# AFR_bar.net
KiCad netlist of a schematic drawn in Altium Designer
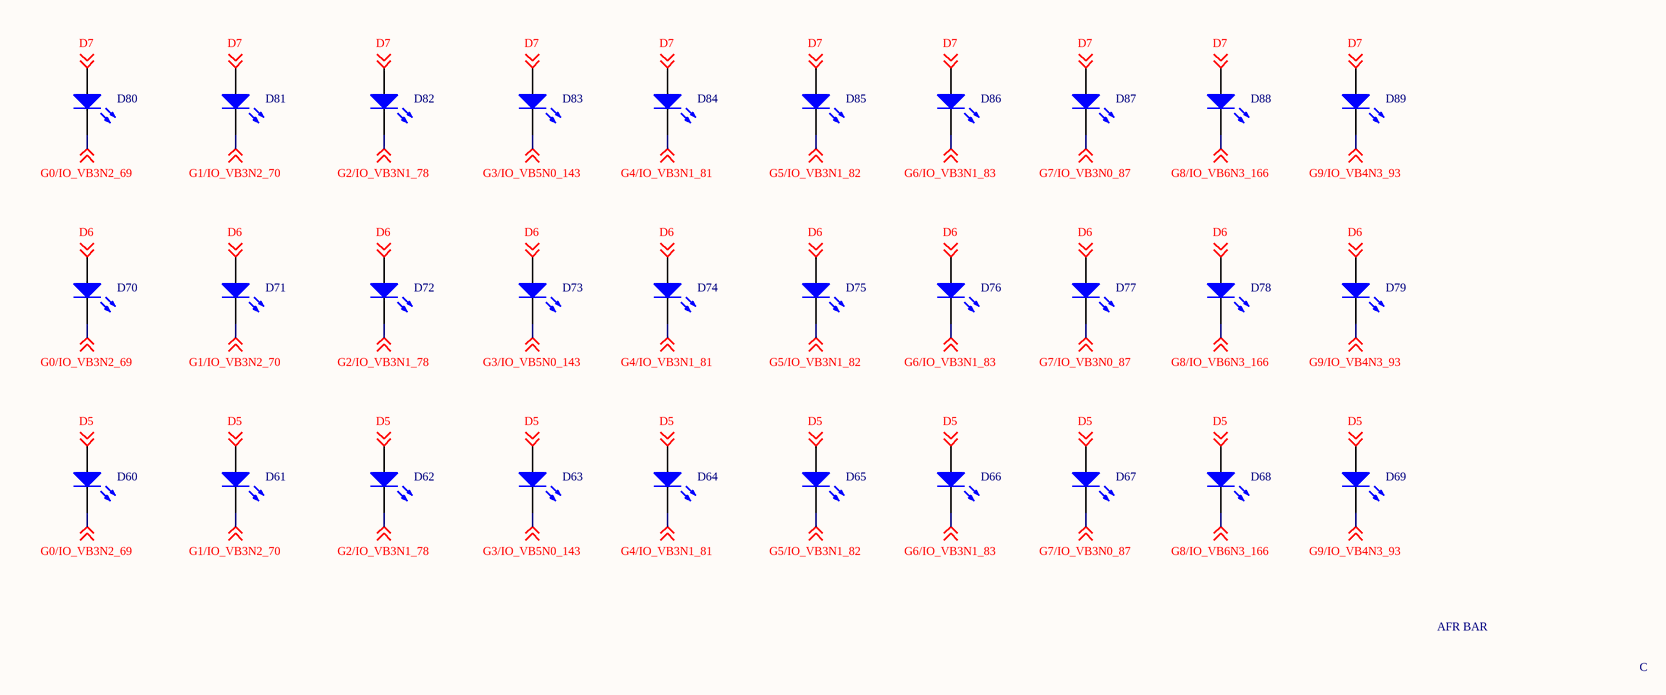
[diagram p0: AFR_bar.SchDoc]

(export (version "E")
  (design (tool "Eeschema 10.0.6"))
  (components
    (comp (ref "D60")
      (value "~")
      (footprint "DIODE_0603")
      (description "Typical INFRARED GaAs LED")
      (fields (field (name "PUBLISHER") "Altium Limited"))
      (libsource (lib "Miscellaneous Devices") (part "LED0"))
    )
    (comp (ref "D61")
      (value "~")
      (footprint "DIODE_0603")
      (description "Typical INFRARED GaAs LED")
      (fields (field (name "PUBLISHER") "Altium Limited"))
      (libsource (lib "Miscellaneous Devices") (part "LED0"))
    )
    (comp (ref "D62")
      (value "~")
      (footprint "DIODE_0603")
      (description "Typical INFRARED GaAs LED")
      (fields (field (name "PUBLISHER") "Altium Limited"))
      (libsource (lib "Miscellaneous Devices") (part "LED0"))
    )
    (comp (ref "D63")
      (value "~")
      (footprint "DIODE_0603")
      (description "Typical INFRARED GaAs LED")
      (fields (field (name "PUBLISHER") "Altium Limited"))
      (libsource (lib "Miscellaneous Devices") (part "LED0"))
    )
    (comp (ref "D64")
      (value "~")
      (footprint "DIODE_0603")
      (description "Typical INFRARED GaAs LED")
      (fields (field (name "PUBLISHER") "Altium Limited"))
      (libsource (lib "Miscellaneous Devices") (part "LED0"))
    )
    (comp (ref "D65")
      (value "~")
      (footprint "DIODE_0603")
      (description "Typical INFRARED GaAs LED")
      (fields (field (name "PUBLISHER") "Altium Limited"))
      (libsource (lib "Miscellaneous Devices") (part "LED0"))
    )
    (comp (ref "D66")
      (value "~")
      (footprint "DIODE_0603")
      (description "Typical INFRARED GaAs LED")
      (fields (field (name "PUBLISHER") "Altium Limited"))
      (libsource (lib "Miscellaneous Devices") (part "LED0"))
    )
    (comp (ref "D67")
      (value "~")
      (footprint "DIODE_0603")
      (description "Typical INFRARED GaAs LED")
      (fields (field (name "PUBLISHER") "Altium Limited"))
      (libsource (lib "Miscellaneous Devices") (part "LED0"))
    )
    (comp (ref "D68")
      (value "~")
      (footprint "DIODE_0603")
      (description "Typical INFRARED GaAs LED")
      (fields (field (name "PUBLISHER") "Altium Limited"))
      (libsource (lib "Miscellaneous Devices") (part "LED0"))
    )
    (comp (ref "D69")
      (value "~")
      (footprint "DIODE_0603")
      (description "Typical INFRARED GaAs LED")
      (fields (field (name "PUBLISHER") "Altium Limited"))
      (libsource (lib "Miscellaneous Devices") (part "LED0"))
    )
    (comp (ref "D70")
      (value "~")
      (footprint "DIODE_0603")
      (description "Typical INFRARED GaAs LED")
      (fields (field (name "PUBLISHER") "Altium Limited"))
      (libsource (lib "Miscellaneous Devices") (part "LED0"))
    )
    (comp (ref "D71")
      (value "~")
      (footprint "DIODE_0603")
      (description "Typical INFRARED GaAs LED")
      (fields (field (name "PUBLISHER") "Altium Limited"))
      (libsource (lib "Miscellaneous Devices") (part "LED0"))
    )
    (comp (ref "D72")
      (value "~")
      (footprint "DIODE_0603")
      (description "Typical INFRARED GaAs LED")
      (fields (field (name "PUBLISHER") "Altium Limited"))
      (libsource (lib "Miscellaneous Devices") (part "LED0"))
    )
    (comp (ref "D73")
      (value "~")
      (footprint "DIODE_0603")
      (description "Typical INFRARED GaAs LED")
      (fields (field (name "PUBLISHER") "Altium Limited"))
      (libsource (lib "Miscellaneous Devices") (part "LED0"))
    )
    (comp (ref "D74")
      (value "~")
      (footprint "DIODE_0603")
      (description "Typical INFRARED GaAs LED")
      (fields (field (name "PUBLISHER") "Altium Limited"))
      (libsource (lib "Miscellaneous Devices") (part "LED0"))
    )
    (comp (ref "D75")
      (value "~")
      (footprint "DIODE_0603")
      (description "Typical INFRARED GaAs LED")
      (fields (field (name "PUBLISHER") "Altium Limited"))
      (libsource (lib "Miscellaneous Devices") (part "LED0"))
    )
    (comp (ref "D76")
      (value "~")
      (footprint "DIODE_0603")
      (description "Typical INFRARED GaAs LED")
      (fields (field (name "PUBLISHER") "Altium Limited"))
      (libsource (lib "Miscellaneous Devices") (part "LED0"))
    )
    (comp (ref "D77")
      (value "~")
      (footprint "DIODE_0603")
      (description "Typical INFRARED GaAs LED")
      (fields (field (name "PUBLISHER") "Altium Limited"))
      (libsource (lib "Miscellaneous Devices") (part "LED0"))
    )
    (comp (ref "D78")
      (value "~")
      (footprint "DIODE_0603")
      (description "Typical INFRARED GaAs LED")
      (fields (field (name "PUBLISHER") "Altium Limited"))
      (libsource (lib "Miscellaneous Devices") (part "LED0"))
    )
    (comp (ref "D79")
      (value "~")
      (footprint "DIODE_0603")
      (description "Typical INFRARED GaAs LED")
      (fields (field (name "PUBLISHER") "Altium Limited"))
      (libsource (lib "Miscellaneous Devices") (part "LED0"))
    )
    (comp (ref "D80")
      (value "~")
      (footprint "DIODE_0603")
      (description "Typical INFRARED GaAs LED")
      (fields (field (name "PUBLISHER") "Altium Limited"))
      (libsource (lib "Miscellaneous Devices") (part "LED0"))
    )
    (comp (ref "D81")
      (value "~")
      (footprint "DIODE_0603")
      (description "Typical INFRARED GaAs LED")
      (fields (field (name "PUBLISHER") "Altium Limited"))
      (libsource (lib "Miscellaneous Devices") (part "LED0"))
    )
    (comp (ref "D82")
      (value "~")
      (footprint "DIODE_0603")
      (description "Typical INFRARED GaAs LED")
      (fields (field (name "PUBLISHER") "Altium Limited"))
      (libsource (lib "Miscellaneous Devices") (part "LED0"))
    )
    (comp (ref "D83")
      (value "~")
      (footprint "DIODE_0603")
      (description "Typical INFRARED GaAs LED")
      (fields (field (name "PUBLISHER") "Altium Limited"))
      (libsource (lib "Miscellaneous Devices") (part "LED0"))
    )
    (comp (ref "D84")
      (value "~")
      (footprint "DIODE_0603")
      (description "Typical INFRARED GaAs LED")
      (fields (field (name "PUBLISHER") "Altium Limited"))
      (libsource (lib "Miscellaneous Devices") (part "LED0"))
    )
    (comp (ref "D85")
      (value "~")
      (footprint "DIODE_0603")
      (description "Typical INFRARED GaAs LED")
      (fields (field (name "PUBLISHER") "Altium Limited"))
      (libsource (lib "Miscellaneous Devices") (part "LED0"))
    )
    (comp (ref "D86")
      (value "~")
      (footprint "DIODE_0603")
      (description "Typical INFRARED GaAs LED")
      (fields (field (name "PUBLISHER") "Altium Limited"))
      (libsource (lib "Miscellaneous Devices") (part "LED0"))
    )
    (comp (ref "D87")
      (value "~")
      (footprint "DIODE_0603")
      (description "Typical INFRARED GaAs LED")
      (fields (field (name "PUBLISHER") "Altium Limited"))
      (libsource (lib "Miscellaneous Devices") (part "LED0"))
    )
    (comp (ref "D88")
      (value "~")
      (footprint "DIODE_0603")
      (description "Typical INFRARED GaAs LED")
      (fields (field (name "PUBLISHER") "Altium Limited"))
      (libsource (lib "Miscellaneous Devices") (part "LED0"))
    )
    (comp (ref "D89")
      (value "~")
      (footprint "DIODE_0603")
      (description "Typical INFRARED GaAs LED")
      (fields (field (name "PUBLISHER") "Altium Limited"))
      (libsource (lib "Miscellaneous Devices") (part "LED0"))
    )
  )
  (nets
    (net (code "1") (name "D5") (class "Default")
      (node (ref "D60") (pin "1") (pinfunction "A_1") (pintype "passive"))
      (node (ref "D61") (pin "1") (pinfunction "A_1") (pintype "passive"))
      (node (ref "D62") (pin "1") (pinfunction "A_1") (pintype "passive"))
      (node (ref "D63") (pin "1") (pinfunction "A_1") (pintype "passive"))
      (node (ref "D64") (pin "1") (pinfunction "A_1") (pintype "passive"))
      (node (ref "D65") (pin "1") (pinfunction "A_1") (pintype "passive"))
      (node (ref "D66") (pin "1") (pinfunction "A_1") (pintype "passive"))
      (node (ref "D67") (pin "1") (pinfunction "A_1") (pintype "passive"))
      (node (ref "D68") (pin "1") (pinfunction "A_1") (pintype "passive"))
      (node (ref "D69") (pin "1") (pinfunction "A_1") (pintype "passive"))
    )
    (net (code "2") (name "D6") (class "Default")
      (node (ref "D70") (pin "1") (pinfunction "A_1") (pintype "passive"))
      (node (ref "D71") (pin "1") (pinfunction "A_1") (pintype "passive"))
      (node (ref "D72") (pin "1") (pinfunction "A_1") (pintype "passive"))
      (node (ref "D73") (pin "1") (pinfunction "A_1") (pintype "passive"))
      (node (ref "D74") (pin "1") (pinfunction "A_1") (pintype "passive"))
      (node (ref "D75") (pin "1") (pinfunction "A_1") (pintype "passive"))
      (node (ref "D76") (pin "1") (pinfunction "A_1") (pintype "passive"))
      (node (ref "D77") (pin "1") (pinfunction "A_1") (pintype "passive"))
      (node (ref "D78") (pin "1") (pinfunction "A_1") (pintype "passive"))
      (node (ref "D79") (pin "1") (pinfunction "A_1") (pintype "passive"))
    )
    (net (code "3") (name "D7") (class "Default")
      (node (ref "D80") (pin "1") (pinfunction "A_1") (pintype "passive"))
      (node (ref "D81") (pin "1") (pinfunction "A_1") (pintype "passive"))
      (node (ref "D82") (pin "1") (pinfunction "A_1") (pintype "passive"))
      (node (ref "D83") (pin "1") (pinfunction "A_1") (pintype "passive"))
      (node (ref "D84") (pin "1") (pinfunction "A_1") (pintype "passive"))
      (node (ref "D85") (pin "1") (pinfunction "A_1") (pintype "passive"))
      (node (ref "D86") (pin "1") (pinfunction "A_1") (pintype "passive"))
      (node (ref "D87") (pin "1") (pinfunction "A_1") (pintype "passive"))
      (node (ref "D88") (pin "1") (pinfunction "A_1") (pintype "passive"))
      (node (ref "D89") (pin "1") (pinfunction "A_1") (pintype "passive"))
    )
    (net (code "4") (name "G0{slash}IO_VB3N2_69") (class "Default")
      (node (ref "D60") (pin "2") (pinfunction "K_2") (pintype "passive"))
      (node (ref "D70") (pin "2") (pinfunction "K_2") (pintype "passive"))
      (node (ref "D80") (pin "2") (pinfunction "K_2") (pintype "passive"))
    )
    (net (code "5") (name "G1{slash}IO_VB3N2_70") (class "Default")
      (node (ref "D61") (pin "2") (pinfunction "K_2") (pintype "passive"))
      (node (ref "D71") (pin "2") (pinfunction "K_2") (pintype "passive"))
      (node (ref "D81") (pin "2") (pinfunction "K_2") (pintype "passive"))
    )
    (net (code "6") (name "G2{slash}IO_VB3N1_78") (class "Default")
      (node (ref "D62") (pin "2") (pinfunction "K_2") (pintype "passive"))
      (node (ref "D72") (pin "2") (pinfunction "K_2") (pintype "passive"))
      (node (ref "D82") (pin "2") (pinfunction "K_2") (pintype "passive"))
    )
    (net (code "7") (name "G3{slash}IO_VB5N0_143") (class "Default")
      (node (ref "D63") (pin "2") (pinfunction "K_2") (pintype "passive"))
      (node (ref "D73") (pin "2") (pinfunction "K_2") (pintype "passive"))
      (node (ref "D83") (pin "2") (pinfunction "K_2") (pintype "passive"))
    )
    (net (code "8") (name "G4{slash}IO_VB3N1_81") (class "Default")
      (node (ref "D64") (pin "2") (pinfunction "K_2") (pintype "passive"))
      (node (ref "D74") (pin "2") (pinfunction "K_2") (pintype "passive"))
      (node (ref "D84") (pin "2") (pinfunction "K_2") (pintype "passive"))
    )
    (net (code "9") (name "G5{slash}IO_VB3N1_82") (class "Default")
      (node (ref "D65") (pin "2") (pinfunction "K_2") (pintype "passive"))
      (node (ref "D75") (pin "2") (pinfunction "K_2") (pintype "passive"))
      (node (ref "D85") (pin "2") (pinfunction "K_2") (pintype "passive"))
    )
    (net (code "10") (name "G6{slash}IO_VB3N1_83") (class "Default")
      (node (ref "D66") (pin "2") (pinfunction "K_2") (pintype "passive"))
      (node (ref "D76") (pin "2") (pinfunction "K_2") (pintype "passive"))
      (node (ref "D86") (pin "2") (pinfunction "K_2") (pintype "passive"))
    )
    (net (code "11") (name "G7{slash}IO_VB3N0_87") (class "Default")
      (node (ref "D67") (pin "2") (pinfunction "K_2") (pintype "passive"))
      (node (ref "D77") (pin "2") (pinfunction "K_2") (pintype "passive"))
      (node (ref "D87") (pin "2") (pinfunction "K_2") (pintype "passive"))
    )
    (net (code "12") (name "G8{slash}IO_VB6N3_166") (class "Default")
      (node (ref "D68") (pin "2") (pinfunction "K_2") (pintype "passive"))
      (node (ref "D78") (pin "2") (pinfunction "K_2") (pintype "passive"))
      (node (ref "D88") (pin "2") (pinfunction "K_2") (pintype "passive"))
    )
    (net (code "13") (name "G9{slash}IO_VB4N3_93") (class "Default")
      (node (ref "D69") (pin "2") (pinfunction "K_2") (pintype "passive"))
      (node (ref "D79") (pin "2") (pinfunction "K_2") (pintype "passive"))
      (node (ref "D89") (pin "2") (pinfunction "K_2") (pintype "passive"))
    )
  )
)
